# OSP_Carrier_V8_DJB.net
KiCad netlist of a schematic drawn in Altium Designer
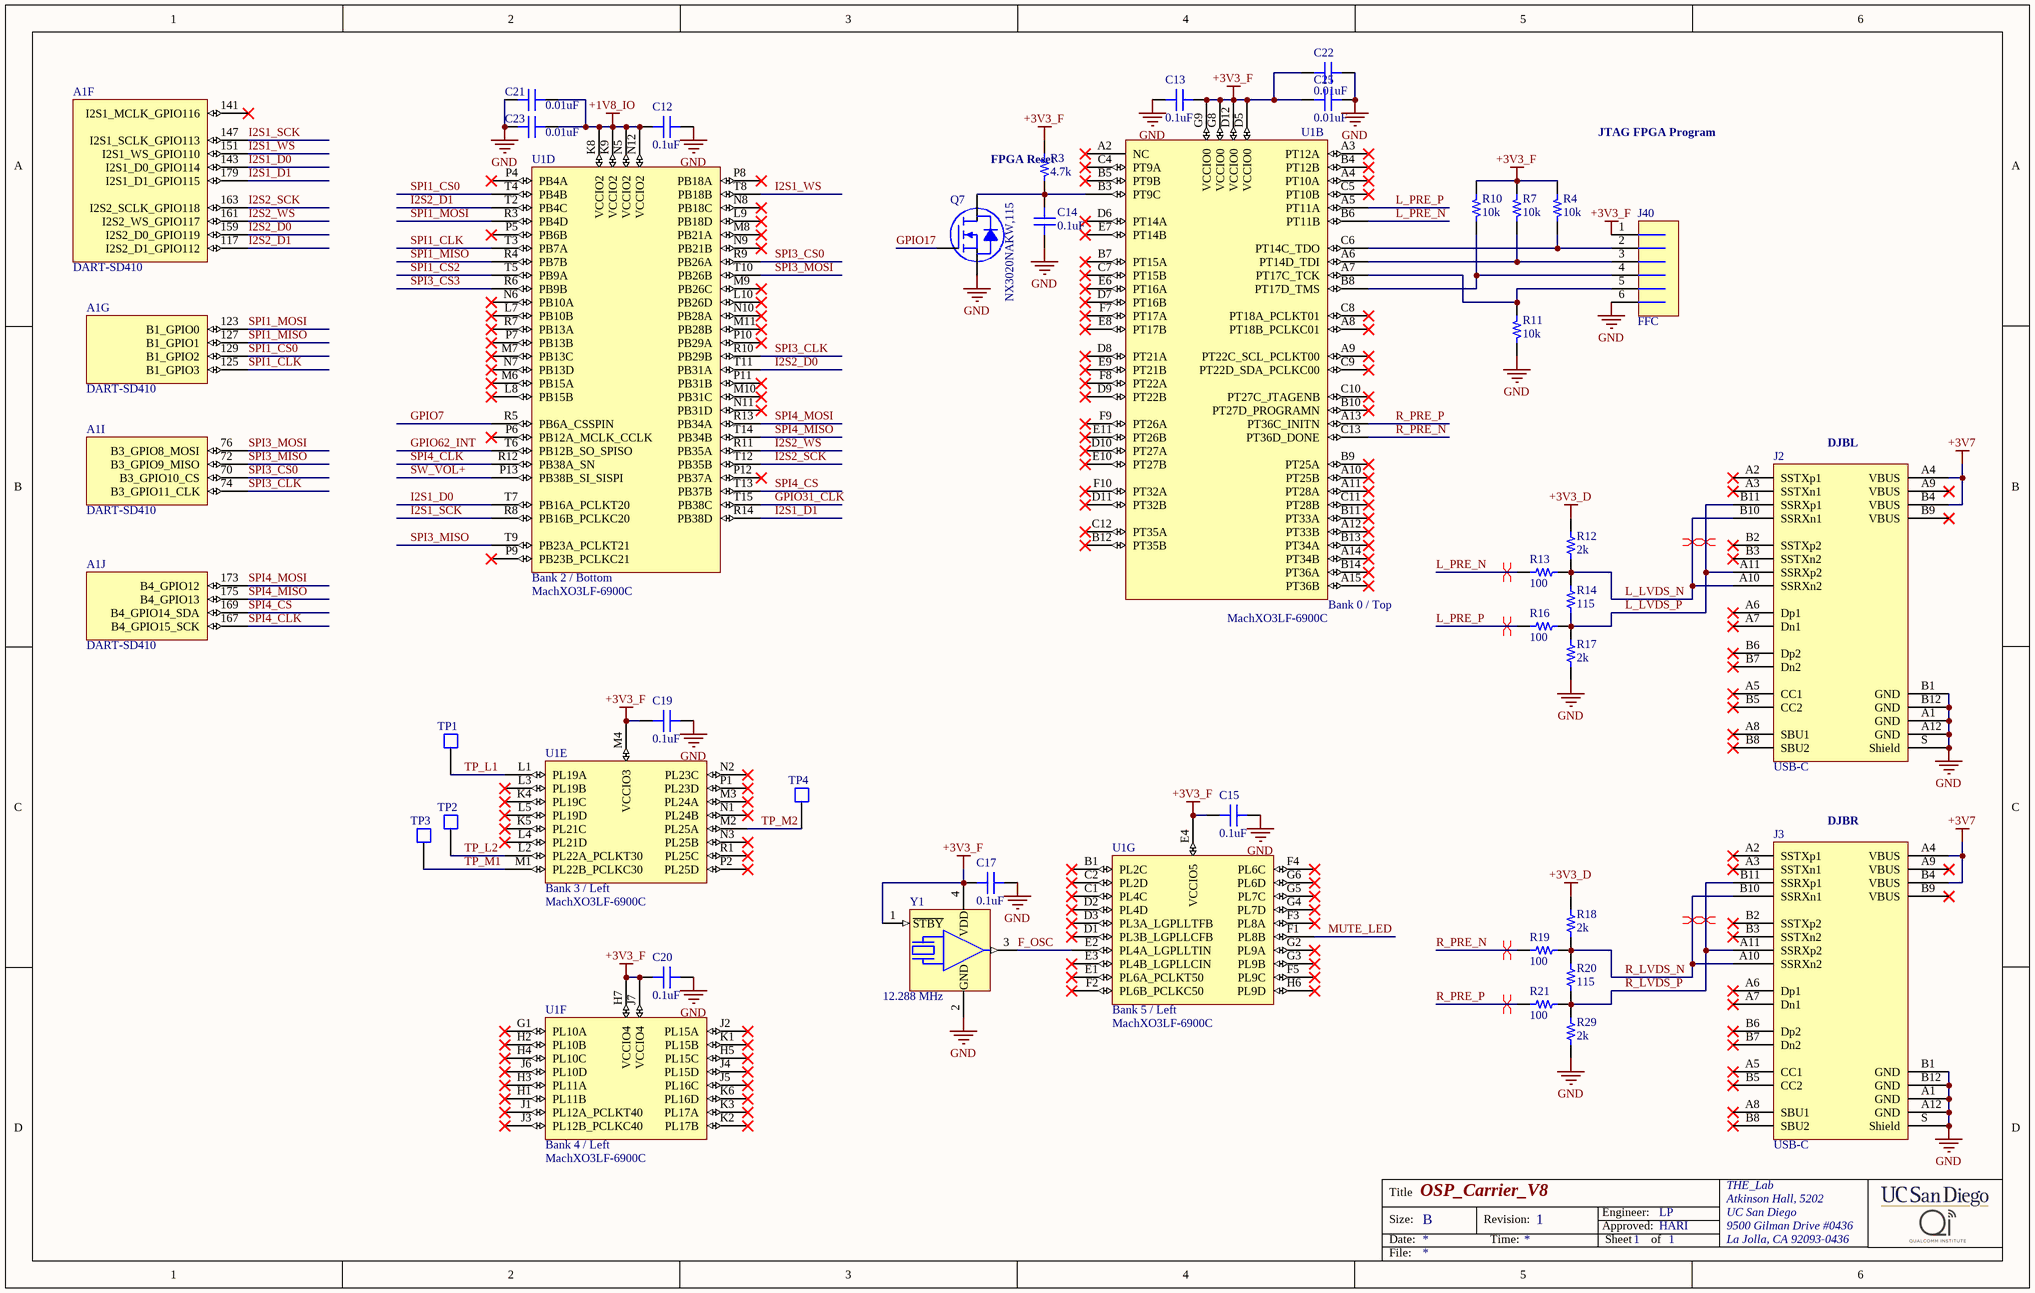
[diagram p0: OSP_Carrier_V8_DJB.SchDoc]

(export (version "E")
  (design (tool "Eeschema 10.0.6"))
  (components
    (comp (ref "A1")
      (value "DART-SD410")
      (footprint "DART-SD410")
      (description "Variscite DART-SD410 System on Module")
      (libsource (lib "DART-SD410") (part "DART-SD410"))
    )
    (comp (ref "C12")
      (value "0.1uF")
      (footprint "CAP 0402/1005")
      (description "CAP CER 0.1UF 50V X7R 0402")
      (fields
        (field (name "PART NUMBER") "C1005X7R1H104K050BB")
        (field (name "MANUFACTURER") "TDK Corporation")
      )
      (libsource (lib "Celestial Library Database") (part "Capacitor"))
    )
    (comp (ref "C13")
      (value "0.1uF")
      (footprint "CAP 0402/1005")
      (description "CAP CER 0.1UF 50V X7R 0402")
      (fields
        (field (name "PART NUMBER") "C1005X7R1H104K050BB")
        (field (name "MANUFACTURER") "TDK Corporation")
      )
      (libsource (lib "Celestial Library Database") (part "Capacitor"))
    )
    (comp (ref "C14")
      (value "0.1uF")
      (footprint "CAP 0402/1005")
      (description "CAP CER 0.1UF 50V X7R 0402")
      (fields
        (field (name "PART NUMBER") "C1005X7R1H104K050BB")
        (field (name "MANUFACTURER") "TDK Corporation")
      )
      (libsource (lib "Celestial Library Database") (part "Capacitor"))
    )
    (comp (ref "C15")
      (value "0.1uF")
      (footprint "CAP 0402/1005")
      (description "CAP CER 0.1UF 50V X7R 0402")
      (fields
        (field (name "PART NUMBER") "C1005X7R1H104K050BB")
        (field (name "MANUFACTURER") "TDK Corporation")
      )
      (libsource (lib "Celestial Library Database") (part "Capacitor"))
    )
    (comp (ref "C17")
      (value "0.1uF")
      (footprint "CAP 0402/1005")
      (description "CAP CER 0.1UF 50V X7R 0402")
      (fields
        (field (name "PART NUMBER") "C1005X7R1H104K050BB")
        (field (name "MANUFACTURER") "TDK Corporation")
      )
      (libsource (lib "Celestial Library Database") (part "Capacitor"))
    )
    (comp (ref "C19")
      (value "0.1uF")
      (footprint "CAP 0402/1005")
      (description "CAP CER 0.1UF 50V X7R 0402")
      (fields
        (field (name "PART NUMBER") "C1005X7R1H104K050BB")
        (field (name "MANUFACTURER") "TDK Corporation")
      )
      (libsource (lib "Celestial Library Database") (part "Capacitor"))
    )
    (comp (ref "C20")
      (value "0.1uF")
      (footprint "CAP 0402/1005")
      (description "CAP CER 0.1UF 50V X7R 0402")
      (fields
        (field (name "PART NUMBER") "C1005X7R1H104K050BB")
        (field (name "MANUFACTURER") "TDK Corporation")
      )
      (libsource (lib "Celestial Library Database") (part "Capacitor"))
    )
    (comp (ref "C21")
      (value "0.01uF")
      (footprint "CAP 0402/1005")
      (description "CAP CER 10000PF 25V X7R 0402")
      (fields (field (name "PART NUMBER") "CC0402KRX7R8BB103") (field (name "MANUFACTURER") "Yageo"))
      (libsource (lib "Celestial Library Database") (part "Capacitor"))
    )
    (comp (ref "C22")
      (value "0.01uF")
      (footprint "CAP 0402/1005")
      (description "CAP CER 10000PF 25V X7R 0402")
      (fields (field (name "PART NUMBER") "CC0402KRX7R8BB103") (field (name "MANUFACTURER") "Yageo"))
      (libsource (lib "Celestial Library Database") (part "Capacitor"))
    )
    (comp (ref "C23")
      (value "0.01uF")
      (footprint "CAP 0402/1005")
      (description "CAP CER 10000PF 25V X7R 0402")
      (fields (field (name "PART NUMBER") "CC0402KRX7R8BB103") (field (name "MANUFACTURER") "Yageo"))
      (libsource (lib "Celestial Library Database") (part "Capacitor"))
    )
    (comp (ref "C25")
      (value "0.01uF")
      (footprint "CAP 0402/1005")
      (description "CAP CER 10000PF 25V X7R 0402")
      (fields (field (name "PART NUMBER") "CC0402KRX7R8BB103") (field (name "MANUFACTURER") "Yageo"))
      (libsource (lib "Celestial Library Database") (part "Capacitor"))
    )
    (comp (ref "J2")
      (value "USB-C")
      (footprint "TE_USB-C_2129691-1")
      (description "TE 2129691-1 USB-C Socket")
      (libsource (lib "OSP_Symbols") (part "TE_USB_C_2129691-1"))
    )
    (comp (ref "J3")
      (value "USB-C")
      (footprint "TE_USB-C_2129691-1")
      (description "TE 2129691-1 USB-C Socket")
      (libsource (lib "OSP_Symbols") (part "TE_USB_C_2129691-1"))
    )
    (comp (ref "J40")
      (value "FFC")
      (footprint "AMPHENOL_HFW6R-1STE1LF")
      (description "Amphenol HFW6R-1STE1LF 6-pin flat flexible cable connector")
      (libsource (lib "OSP_Symbols") (part "AMPHENOL_HFW6R-1STE1LF"))
    )
    (comp (ref "Q7")
      (value "NX3020NAKW,115")
      (footprint "NXP SOT-323-3")
      (description "MOSFET N-CH 30V 180MA SOT323")
      (libsource (lib "Celestial Library Database") (part "NXP MOSFET N-CH SOT-23-3"))
    )
    (comp (ref "R3")
      (value "4.7k")
      (footprint "RES 0402/1005")
      (description "RES SMD 4.7K OHM 1% 1/10W 0402")
      (fields
        (field (name "PART NUMBER") "ERJ-2RKF4701X")
        (field (name "MANUFACTURER") "Panasonic Electronic Components")
      )
      (libsource (lib "Celestial Library Database") (part "Resistor"))
    )
    (comp (ref "R4")
      (value "10k")
      (footprint "RES 0402/1005")
      (description "RES SMD 10K OHM 1% 1/10W 0402")
      (fields
        (field (name "PART NUMBER") "ERJ-2RKF1002X")
        (field (name "MANUFACTURER") "Panasonic Electronic Components")
      )
      (libsource (lib "Celestial Library Database") (part "Resistor"))
    )
    (comp (ref "R7")
      (value "10k")
      (footprint "RES 0402/1005")
      (description "RES SMD 10K OHM 1% 1/10W 0402")
      (fields
        (field (name "PART NUMBER") "ERJ-2RKF1002X")
        (field (name "MANUFACTURER") "Panasonic Electronic Components")
      )
      (libsource (lib "Celestial Library Database") (part "Resistor"))
    )
    (comp (ref "R10")
      (value "10k")
      (footprint "RES 0402/1005")
      (description "RES SMD 10K OHM 1% 1/10W 0402")
      (fields
        (field (name "PART NUMBER") "ERJ-2RKF1002X")
        (field (name "MANUFACTURER") "Panasonic Electronic Components")
      )
      (libsource (lib "Celestial Library Database") (part "Resistor"))
    )
    (comp (ref "R11")
      (value "10k")
      (footprint "RES 0402/1005")
      (description "RES SMD 10K OHM 1% 1/10W 0402")
      (fields
        (field (name "PART NUMBER") "ERJ-2RKF1002X")
        (field (name "MANUFACTURER") "Panasonic Electronic Components")
      )
      (libsource (lib "Celestial Library Database") (part "Resistor"))
    )
    (comp (ref "R12")
      (value "2k")
      (footprint "RES 0402/1005")
      (description "RES SMD 2K OHM 1% 1/10W 0402")
      (fields
        (field (name "PART NUMBER") "ERJ-2RKF2001X")
        (field (name "MANUFACTURER") "Panasonic Electronic Components")
      )
      (libsource (lib "Celestial Library Database") (part "Resistor"))
    )
    (comp (ref "R13")
      (value "100")
      (footprint "RES 0402/1005")
      (description "RES SMD 100 OHM 1% 1/10W 0402")
      (fields
        (field (name "PART NUMBER") "ERJ-2RKF1000X")
        (field (name "MANUFACTURER") "Panasonic Electronic Components")
      )
      (libsource (lib "Celestial Library Database") (part "Resistor"))
    )
    (comp (ref "R14")
      (value "115")
      (footprint "RES 0402/1005")
      (description "RES SMD 115 OHM 1% 1/10W 0402")
      (fields
        (field (name "PART NUMBER") "ERJ-2RKF1150X")
        (field (name "MANUFACTURER") "Panasonic Electronic Components")
      )
      (libsource (lib "Celestial Library Database") (part "Resistor"))
    )
    (comp (ref "R16")
      (value "100")
      (footprint "RES 0402/1005")
      (description "RES SMD 100 OHM 1% 1/10W 0402")
      (fields
        (field (name "PART NUMBER") "ERJ-2RKF1000X")
        (field (name "MANUFACTURER") "Panasonic Electronic Components")
      )
      (libsource (lib "Celestial Library Database") (part "Resistor"))
    )
    (comp (ref "R17")
      (value "2k")
      (footprint "RES 0402/1005")
      (description "RES SMD 2K OHM 1% 1/10W 0402")
      (fields
        (field (name "PART NUMBER") "ERJ-2RKF2001X")
        (field (name "MANUFACTURER") "Panasonic Electronic Components")
      )
      (libsource (lib "Celestial Library Database") (part "Resistor"))
    )
    (comp (ref "R18")
      (value "2k")
      (footprint "RES 0402/1005")
      (description "RES SMD 2K OHM 1% 1/10W 0402")
      (fields
        (field (name "PART NUMBER") "ERJ-2RKF2001X")
        (field (name "MANUFACTURER") "Panasonic Electronic Components")
      )
      (libsource (lib "Celestial Library Database") (part "Resistor"))
    )
    (comp (ref "R19")
      (value "100")
      (footprint "RES 0402/1005")
      (description "RES SMD 100 OHM 1% 1/10W 0402")
      (fields
        (field (name "PART NUMBER") "ERJ-2RKF1000X")
        (field (name "MANUFACTURER") "Panasonic Electronic Components")
      )
      (libsource (lib "Celestial Library Database") (part "Resistor"))
    )
    (comp (ref "R20")
      (value "115")
      (footprint "RES 0402/1005")
      (description "RES SMD 115 OHM 1% 1/10W 0402")
      (fields
        (field (name "PART NUMBER") "ERJ-2RKF1150X")
        (field (name "MANUFACTURER") "Panasonic Electronic Components")
      )
      (libsource (lib "Celestial Library Database") (part "Resistor"))
    )
    (comp (ref "R21")
      (value "100")
      (footprint "RES 0402/1005")
      (description "RES SMD 100 OHM 1% 1/10W 0402")
      (fields
        (field (name "PART NUMBER") "ERJ-2RKF1000X")
        (field (name "MANUFACTURER") "Panasonic Electronic Components")
      )
      (libsource (lib "Celestial Library Database") (part "Resistor"))
    )
    (comp (ref "R29")
      (value "2k")
      (footprint "RES 0402/1005")
      (description "RES SMD 2K OHM 1% 1/10W 0402")
      (fields
        (field (name "PART NUMBER") "ERJ-2RKF2001X")
        (field (name "MANUFACTURER") "Panasonic Electronic Components")
      )
      (libsource (lib "Celestial Library Database") (part "Resistor"))
    )
    (comp (ref "TP1")
      (value "TP_SMD_1MM_SQ")
      (footprint "TP_SMD_1MM_SQ")
      (description "1mm Square SMD Test Point")
      (libsource (lib "OSP_Symbols") (part "TP_SMD_1MM_SQ"))
    )
    (comp (ref "TP2")
      (value "TP_SMD_1MM_SQ")
      (footprint "TP_SMD_1MM_SQ")
      (description "1mm Square SMD Test Point")
      (libsource (lib "OSP_Symbols") (part "TP_SMD_1MM_SQ"))
    )
    (comp (ref "TP3")
      (value "TP_SMD_1MM_SQ")
      (footprint "TP_SMD_1MM_SQ")
      (description "1mm Square SMD Test Point")
      (libsource (lib "OSP_Symbols") (part "TP_SMD_1MM_SQ"))
    )
    (comp (ref "TP4")
      (value "TP_SMD_1MM_SQ")
      (footprint "TP_SMD_1MM_SQ")
      (description "1mm Square SMD Test Point")
      (libsource (lib "OSP_Symbols") (part "TP_SMD_1MM_SQ"))
    )
    (comp (ref "U1")
      (value "MachXO3LF-6900C")
      (footprint "LCMXO3_caBGA_BG256")
      (description "Lattice MachXO3LF-6900C-5BG256C FPGA")
      (libsource (lib "") (part "LCMXO3LF-6900C-XBG256X_1"))
    )
    (comp (ref "Y1")
      (value "12.288 MHz")
      (footprint "OSC_2.5x2.0mm")
      (description "Microchip 12.288 MHz SMD MEMS Oscillator")
      (libsource (lib "OSP_Symbols") (part "MC_DSC1033DI2-012.2880"))
    )
  )
  (nets
    (net (code "1") (name "+1V8_IO") (class "Default")
      (node (ref "C12") (pin "2") (pinfunction "2_2") (pintype "passive"))
      (node (ref "C21") (pin "1") (pinfunction "1_1") (pintype "passive"))
      (node (ref "C23") (pin "1") (pinfunction "1_1") (pintype "passive"))
      (node (ref "U1") (pin "K8") (pinfunction "VCCIO2_K8") (pintype "bidirectional"))
      (node (ref "U1") (pin "K9") (pinfunction "VCCIO2_K9") (pintype "bidirectional"))
      (node (ref "U1") (pin "N12") (pinfunction "VCCIO2_N12") (pintype "bidirectional"))
      (node (ref "U1") (pin "N5") (pinfunction "VCCIO2_N5") (pintype "bidirectional"))
    )
    (net (code "2") (name "+3V3_D") (class "Default")
      (node (ref "R12") (pin "2") (pinfunction "2_2") (pintype "passive"))
      (node (ref "R18") (pin "2") (pinfunction "2_2") (pintype "passive"))
    )
    (net (code "3") (name "+3V3_F") (class "Default")
      (node (ref "C13") (pin "2") (pinfunction "2_2") (pintype "passive"))
      (node (ref "C15") (pin "2") (pinfunction "2_2") (pintype "passive"))
      (node (ref "C17") (pin "2") (pinfunction "2_2") (pintype "passive"))
      (node (ref "C19") (pin "2") (pinfunction "2_2") (pintype "passive"))
      (node (ref "C20") (pin "2") (pinfunction "2_2") (pintype "passive"))
      (node (ref "C22") (pin "1") (pinfunction "1_1") (pintype "passive"))
      (node (ref "C25") (pin "1") (pinfunction "1_1") (pintype "passive"))
      (node (ref "J40") (pin "1") (pintype "passive"))
      (node (ref "R10") (pin "2") (pinfunction "2_2") (pintype "passive"))
      (node (ref "R3") (pin "2") (pinfunction "2_2") (pintype "passive"))
      (node (ref "R4") (pin "2") (pinfunction "2_2") (pintype "passive"))
      (node (ref "R7") (pin "2") (pinfunction "2_2") (pintype "passive"))
      (node (ref "U1") (pin "D12") (pinfunction "VCCIO0_D12") (pintype "bidirectional"))
      (node (ref "U1") (pin "D5") (pinfunction "VCCIO0_D5") (pintype "bidirectional"))
      (node (ref "U1") (pin "E4") (pinfunction "VCCIO5_E4") (pintype "bidirectional"))
      (node (ref "U1") (pin "G8") (pinfunction "VCCIO0_G8") (pintype "bidirectional"))
      (node (ref "U1") (pin "G9") (pinfunction "VCCIO0_G9") (pintype "bidirectional"))
      (node (ref "U1") (pin "H7") (pinfunction "VCCIO4_H7") (pintype "bidirectional"))
      (node (ref "U1") (pin "J7") (pinfunction "VCCIO4_J7") (pintype "bidirectional"))
      (node (ref "U1") (pin "M4") (pinfunction "VCCIO3_M4") (pintype "bidirectional"))
      (node (ref "Y1") (pin "1") (pinfunction "~{STBY}_1") (pintype "input"))
      (node (ref "Y1") (pin "4") (pinfunction "VDD_4") (pintype "power_in"))
    )
    (net (code "4") (name "+3V7") (class "Default")
      (node (ref "J2") (pin "A4") (pinfunction "VBUS_A4") (pintype "passive"))
      (node (ref "J2") (pin "B4") (pinfunction "VBUS_B4") (pintype "passive"))
      (node (ref "J3") (pin "A4") (pinfunction "VBUS_A4") (pintype "passive"))
      (node (ref "J3") (pin "B4") (pinfunction "VBUS_B4") (pintype "passive"))
    )
    (net (code "5") (name "/F_OSC") (class "Default")
      (node (ref "U1") (pin "E2") (pinfunction "PL4A_LGPLLTIN_E2") (pintype "bidirectional"))
      (node (ref "Y1") (pin "3") (pinfunction "OUT_3") (pintype "output"))
    )
    (net (code "6") (name "/GPIO7") (class "Default")
      (node (ref "U1") (pin "R5") (pinfunction "PB6A_CSSPIN_R5") (pintype "bidirectional"))
    )
    (net (code "7") (name "/GPIO17") (class "Default")
      (node (ref "Q7") (pin "1") (pinfunction "G_1") (pintype "passive"))
    )
    (net (code "8") (name "/GPIO31_CLK") (class "Default")
      (node (ref "U1") (pin "T15") (pinfunction "PB38C_T15") (pintype "bidirectional"))
    )
    (net (code "9") (name "/GPIO62_INT") (class "Default")
      (node (ref "U1") (pin "T6") (pinfunction "PB12B_SO_SPISO_T6") (pintype "bidirectional"))
    )
    (net (code "10") (name "/I2S1_D0") (class "Default")
      (node (ref "A1") (pin "143") (pinfunction "I2S1_D0_GPIO114_143") (pintype "bidirectional"))
      (node (ref "U1") (pin "T7") (pinfunction "PB16A_PCLKT20_T7") (pintype "bidirectional"))
    )
    (net (code "11") (name "/I2S1_D1") (class "Default")
      (node (ref "A1") (pin "179") (pinfunction "I2S1_D1_GPIO115_179") (pintype "bidirectional"))
      (node (ref "U1") (pin "R14") (pinfunction "PB38D_R14") (pintype "bidirectional"))
    )
    (net (code "12") (name "/I2S1_SCK") (class "Default")
      (node (ref "A1") (pin "147") (pinfunction "I2S1_SCLK_GPIO113_147") (pintype "bidirectional"))
      (node (ref "U1") (pin "R8") (pinfunction "PB16B_PCLKC20_R8") (pintype "bidirectional"))
    )
    (net (code "13") (name "/I2S1_WS") (class "Default")
      (node (ref "A1") (pin "151") (pinfunction "I2S1_WS_GPIO110_151") (pintype "bidirectional"))
      (node (ref "U1") (pin "T8") (pinfunction "PB18B_T8") (pintype "bidirectional"))
    )
    (net (code "14") (name "/I2S2_D0") (class "Default")
      (node (ref "A1") (pin "159") (pinfunction "I2S2_D0_GPIO119_159") (pintype "bidirectional"))
      (node (ref "U1") (pin "T11") (pinfunction "PB31A_T11") (pintype "bidirectional"))
    )
    (net (code "15") (name "/I2S2_D1") (class "Default")
      (node (ref "A1") (pin "117") (pinfunction "I2S2_D1_GPIO112_117") (pintype "bidirectional"))
      (node (ref "U1") (pin "T2") (pinfunction "PB4C_T2") (pintype "bidirectional"))
    )
    (net (code "16") (name "/I2S2_SCK") (class "Default")
      (node (ref "A1") (pin "163") (pinfunction "I2S2_SCLK_GPIO118_163") (pintype "bidirectional"))
      (node (ref "U1") (pin "T12") (pinfunction "PB35B_T12") (pintype "bidirectional"))
    )
    (net (code "17") (name "/I2S2_WS") (class "Default")
      (node (ref "A1") (pin "161") (pinfunction "I2S2_WS_GPIO117_161") (pintype "bidirectional"))
      (node (ref "U1") (pin "R11") (pinfunction "PB35A_R11") (pintype "bidirectional"))
    )
    (net (code "18") (name "/L_LVDS_N") (class "Default")
      (node (ref "J2") (pin "A10") (pinfunction "SSRXn2_A10") (pintype "passive"))
      (node (ref "J2") (pin "B10") (pinfunction "SSRXn1_B10") (pintype "passive"))
      (node (ref "R12") (pin "1") (pinfunction "1_1") (pintype "passive"))
      (node (ref "R13") (pin "2") (pinfunction "2_2") (pintype "passive"))
      (node (ref "R14") (pin "2") (pinfunction "2_2") (pintype "passive"))
    )
    (net (code "19") (name "/L_LVDS_P") (class "Default")
      (node (ref "J2") (pin "A11") (pinfunction "SSRXp2_A11") (pintype "passive"))
      (node (ref "J2") (pin "B11") (pinfunction "SSRXp1_B11") (pintype "passive"))
      (node (ref "R14") (pin "1") (pinfunction "1_1") (pintype "passive"))
      (node (ref "R16") (pin "2") (pinfunction "2_2") (pintype "passive"))
      (node (ref "R17") (pin "2") (pinfunction "2_2") (pintype "passive"))
    )
    (net (code "20") (name "/L_PRE_N") (class "Default")
      (node (ref "R13") (pin "1") (pinfunction "1_1") (pintype "passive"))
      (node (ref "U1") (pin "B6") (pinfunction "PT11B_B6") (pintype "bidirectional"))
    )
    (net (code "21") (name "/L_PRE_P") (class "Default")
      (node (ref "R16") (pin "1") (pinfunction "1_1") (pintype "passive"))
      (node (ref "U1") (pin "A5") (pinfunction "PT11A_A5") (pintype "bidirectional"))
    )
    (net (code "22") (name "/MUTE_LED") (class "Default")
      (node (ref "U1") (pin "F1") (pinfunction "PL8B_F1") (pintype "bidirectional"))
    )
    (net (code "23") (name "/R_LVDS_N") (class "Default")
      (node (ref "J3") (pin "A10") (pinfunction "SSRXn2_A10") (pintype "passive"))
      (node (ref "J3") (pin "B10") (pinfunction "SSRXn1_B10") (pintype "passive"))
      (node (ref "R18") (pin "1") (pinfunction "1_1") (pintype "passive"))
      (node (ref "R19") (pin "2") (pinfunction "2_2") (pintype "passive"))
      (node (ref "R20") (pin "2") (pinfunction "2_2") (pintype "passive"))
    )
    (net (code "24") (name "/R_LVDS_P") (class "Default")
      (node (ref "J3") (pin "A11") (pinfunction "SSRXp2_A11") (pintype "passive"))
      (node (ref "J3") (pin "B11") (pinfunction "SSRXp1_B11") (pintype "passive"))
      (node (ref "R20") (pin "1") (pinfunction "1_1") (pintype "passive"))
      (node (ref "R21") (pin "2") (pinfunction "2_2") (pintype "passive"))
      (node (ref "R29") (pin "2") (pinfunction "2_2") (pintype "passive"))
    )
    (net (code "25") (name "/R_PRE_N") (class "Default")
      (node (ref "R19") (pin "1") (pinfunction "1_1") (pintype "passive"))
      (node (ref "U1") (pin "C13") (pinfunction "PT36D_DONE_C13") (pintype "bidirectional"))
    )
    (net (code "26") (name "/R_PRE_P") (class "Default")
      (node (ref "R21") (pin "1") (pinfunction "1_1") (pintype "passive"))
      (node (ref "U1") (pin "A13") (pinfunction "PT36C_INITN_A13") (pintype "bidirectional"))
    )
    (net (code "27") (name "/SPI1_CLK") (class "Default")
      (node (ref "A1") (pin "125") (pinfunction "B1_GPIO3_125") (pintype "bidirectional"))
      (node (ref "U1") (pin "T3") (pinfunction "PB7A_T3") (pintype "bidirectional"))
    )
    (net (code "28") (name "/SPI1_CS0") (class "Default")
      (node (ref "A1") (pin "129") (pinfunction "B1_GPIO2_129") (pintype "bidirectional"))
      (node (ref "U1") (pin "T4") (pinfunction "PB4B_T4") (pintype "bidirectional"))
    )
    (net (code "29") (name "/SPI1_CS2") (class "Default")
      (node (ref "U1") (pin "T5") (pinfunction "PB9A_T5") (pintype "bidirectional"))
    )
    (net (code "30") (name "/SPI1_MISO") (class "Default")
      (node (ref "A1") (pin "127") (pinfunction "B1_GPIO1_127") (pintype "bidirectional"))
      (node (ref "U1") (pin "R4") (pinfunction "PB7B_R4") (pintype "bidirectional"))
    )
    (net (code "31") (name "/SPI1_MOSI") (class "Default")
      (node (ref "A1") (pin "123") (pinfunction "B1_GPIO0_123") (pintype "bidirectional"))
      (node (ref "U1") (pin "R3") (pinfunction "PB4D_R3") (pintype "bidirectional"))
    )
    (net (code "32") (name "/SPI3_CLK") (class "Default")
      (node (ref "A1") (pin "74") (pinfunction "B3_GPIO11_CLK_74") (pintype "bidirectional"))
      (node (ref "U1") (pin "R10") (pinfunction "PB29B_R10") (pintype "bidirectional"))
    )
    (net (code "33") (name "/SPI3_CS0") (class "Default")
      (node (ref "A1") (pin "70") (pinfunction "B3_GPIO10_CS_70") (pintype "bidirectional"))
      (node (ref "U1") (pin "R9") (pinfunction "PB26A_R9") (pintype "bidirectional"))
    )
    (net (code "34") (name "/SPI3_CS3") (class "Default")
      (node (ref "U1") (pin "R6") (pinfunction "PB9B_R6") (pintype "bidirectional"))
    )
    (net (code "35") (name "/SPI3_MISO") (class "Default")
      (node (ref "A1") (pin "72") (pinfunction "B3_GPIO9_MISO_72") (pintype "bidirectional"))
      (node (ref "U1") (pin "T9") (pinfunction "PB23A_PCLKT21_T9") (pintype "bidirectional"))
    )
    (net (code "36") (name "/SPI3_MOSI") (class "Default")
      (node (ref "A1") (pin "76") (pinfunction "B3_GPIO8_MOSI_76") (pintype "bidirectional"))
      (node (ref "U1") (pin "T10") (pinfunction "PB26B_T10") (pintype "bidirectional"))
    )
    (net (code "37") (name "/SPI4_CLK") (class "Default")
      (node (ref "A1") (pin "167") (pinfunction "B4_GPIO15_SCK_167") (pintype "bidirectional"))
      (node (ref "U1") (pin "R12") (pinfunction "PB38A_SN_R12") (pintype "bidirectional"))
    )
    (net (code "38") (name "/SPI4_CS") (class "Default")
      (node (ref "A1") (pin "169") (pinfunction "B4_GPIO14_SDA_169") (pintype "bidirectional"))
      (node (ref "U1") (pin "T13") (pinfunction "PB37B_T13") (pintype "bidirectional"))
    )
    (net (code "39") (name "/SPI4_MISO") (class "Default")
      (node (ref "A1") (pin "175") (pinfunction "B4_GPIO13_175") (pintype "bidirectional"))
      (node (ref "U1") (pin "T14") (pinfunction "PB34B_T14") (pintype "bidirectional"))
    )
    (net (code "40") (name "/SPI4_MOSI") (class "Default")
      (node (ref "A1") (pin "173") (pinfunction "B4_GPIO12_173") (pintype "bidirectional"))
      (node (ref "U1") (pin "R13") (pinfunction "PB34A_R13") (pintype "bidirectional"))
    )
    (net (code "41") (name "/SW_VOL+") (class "Default")
      (node (ref "U1") (pin "P13") (pinfunction "PB38B_SI_SISPI_P13") (pintype "bidirectional"))
    )
    (net (code "42") (name "/TP_L1") (class "Default")
      (node (ref "TP1") (pin "1") (pintype "passive"))
      (node (ref "U1") (pin "L1") (pinfunction "PL19A_L1") (pintype "bidirectional"))
    )
    (net (code "43") (name "/TP_L2") (class "Default")
      (node (ref "TP2") (pin "1") (pintype "passive"))
      (node (ref "U1") (pin "L2") (pinfunction "PL22A_PCLKT30_L2") (pintype "bidirectional"))
    )
    (net (code "44") (name "/TP_M1") (class "Default")
      (node (ref "TP3") (pin "1") (pintype "passive"))
      (node (ref "U1") (pin "M1") (pinfunction "PL22B_PCLKC30_M1") (pintype "bidirectional"))
    )
    (net (code "45") (name "/TP_M2") (class "Default")
      (node (ref "TP4") (pin "1") (pintype "passive"))
      (node (ref "U1") (pin "M2") (pinfunction "PL25A_M2") (pintype "bidirectional"))
    )
    (net (code "46") (name "GND") (class "Default")
      (node (ref "C12") (pin "1") (pinfunction "1_1") (pintype "passive"))
      (node (ref "C13") (pin "1") (pinfunction "1_1") (pintype "passive"))
      (node (ref "C14") (pin "2") (pinfunction "2_2") (pintype "passive"))
      (node (ref "C15") (pin "1") (pinfunction "1_1") (pintype "passive"))
      (node (ref "C17") (pin "1") (pinfunction "1_1") (pintype "passive"))
      (node (ref "C19") (pin "1") (pinfunction "1_1") (pintype "passive"))
      (node (ref "C20") (pin "1") (pinfunction "1_1") (pintype "passive"))
      (node (ref "C21") (pin "2") (pinfunction "2_2") (pintype "passive"))
      (node (ref "C22") (pin "2") (pinfunction "2_2") (pintype "passive"))
      (node (ref "C23") (pin "2") (pinfunction "2_2") (pintype "passive"))
      (node (ref "C25") (pin "2") (pinfunction "2_2") (pintype "passive"))
      (node (ref "J2") (pin "A1") (pinfunction "GND_A1") (pintype "passive"))
      (node (ref "J2") (pin "A12") (pinfunction "GND_A12") (pintype "passive"))
      (node (ref "J2") (pin "B1") (pinfunction "GND_B1") (pintype "passive"))
      (node (ref "J2") (pin "B12") (pinfunction "GND_B12") (pintype "passive"))
      (node (ref "J2") (pin "S") (pinfunction "Shield_S") (pintype "passive"))
      (node (ref "J3") (pin "A1") (pinfunction "GND_A1") (pintype "passive"))
      (node (ref "J3") (pin "A12") (pinfunction "GND_A12") (pintype "passive"))
      (node (ref "J3") (pin "B1") (pinfunction "GND_B1") (pintype "passive"))
      (node (ref "J3") (pin "B12") (pinfunction "GND_B12") (pintype "passive"))
      (node (ref "J3") (pin "S") (pinfunction "Shield_S") (pintype "passive"))
      (node (ref "J40") (pin "6") (pintype "passive"))
      (node (ref "Q7") (pin "3") (pinfunction "S_3") (pintype "passive"))
      (node (ref "R11") (pin "1") (pinfunction "1_1") (pintype "passive"))
      (node (ref "R17") (pin "1") (pinfunction "1_1") (pintype "passive"))
      (node (ref "R29") (pin "1") (pinfunction "1_1") (pintype "passive"))
      (node (ref "Y1") (pin "2") (pinfunction "GND_2") (pintype "power_in"))
    )
    (net (code "47") (name "Net-(Q7-D)") (class "Default")
      (node (ref "C14") (pin "1") (pinfunction "1_1") (pintype "passive"))
      (node (ref "Q7") (pin "2") (pinfunction "D_2") (pintype "passive"))
      (node (ref "R3") (pin "1") (pinfunction "1_1") (pintype "passive"))
      (node (ref "U1") (pin "B3") (pinfunction "PT9C_B3") (pintype "bidirectional"))
    )
    (net (code "48") (name "Net-(U1B-PT14C_TDO)") (class "Default")
      (node (ref "J40") (pin "2") (pintype "passive"))
      (node (ref "R4") (pin "1") (pinfunction "1_1") (pintype "passive"))
      (node (ref "U1") (pin "C6") (pinfunction "PT14C_TDO_C6") (pintype "bidirectional"))
    )
    (net (code "49") (name "Net-(U1B-PT14D_TDI)") (class "Default")
      (node (ref "J40") (pin "3") (pintype "passive"))
      (node (ref "R7") (pin "1") (pinfunction "1_1") (pintype "passive"))
      (node (ref "U1") (pin "A6") (pinfunction "PT14D_TDI_A6") (pintype "bidirectional"))
    )
    (net (code "50") (name "Net-(U1B-PT17C_TCK)") (class "Default")
      (node (ref "J40") (pin "5") (pintype "passive"))
      (node (ref "R11") (pin "2") (pinfunction "2_2") (pintype "passive"))
      (node (ref "U1") (pin "A7") (pinfunction "PT17C_TCK_A7") (pintype "bidirectional"))
    )
    (net (code "51") (name "Net-(U1B-PT17D_TMS)") (class "Default")
      (node (ref "J40") (pin "4") (pintype "passive"))
      (node (ref "R10") (pin "1") (pinfunction "1_1") (pintype "passive"))
      (node (ref "U1") (pin "B8") (pinfunction "PT17D_TMS_B8") (pintype "bidirectional"))
    )
    (net (code "52") (name "unconnected-(A1F-I2S1_MCLK_GPIO116-Pad141)") (class "Default")
      (node (ref "A1") (pin "141") (pinfunction "I2S1_MCLK_GPIO116_141") (pintype "bidirectional+no_connect"))
    )
    (net (code "53") (name "unconnected-(J2-CC1-PadA5)") (class "Default")
      (node (ref "J2") (pin "A5") (pinfunction "CC1_A5") (pintype "passive+no_connect"))
    )
    (net (code "54") (name "unconnected-(J2-CC2-PadB5)") (class "Default")
      (node (ref "J2") (pin "B5") (pinfunction "CC2_B5") (pintype "passive+no_connect"))
    )
    (net (code "55") (name "unconnected-(J2-Dn1-PadA7)") (class "Default")
      (node (ref "J2") (pin "A7") (pinfunction "Dn1_A7") (pintype "passive+no_connect"))
    )
    (net (code "56") (name "unconnected-(J2-Dn2-PadB7)") (class "Default")
      (node (ref "J2") (pin "B7") (pinfunction "Dn2_B7") (pintype "passive+no_connect"))
    )
    (net (code "57") (name "unconnected-(J2-Dp1-PadA6)") (class "Default")
      (node (ref "J2") (pin "A6") (pinfunction "Dp1_A6") (pintype "passive+no_connect"))
    )
    (net (code "58") (name "unconnected-(J2-Dp2-PadB6)") (class "Default")
      (node (ref "J2") (pin "B6") (pinfunction "Dp2_B6") (pintype "passive+no_connect"))
    )
    (net (code "59") (name "unconnected-(J2-SBU1-PadA8)") (class "Default")
      (node (ref "J2") (pin "A8") (pinfunction "SBU1_A8") (pintype "passive+no_connect"))
    )
    (net (code "60") (name "unconnected-(J2-SBU2-PadB8)") (class "Default")
      (node (ref "J2") (pin "B8") (pinfunction "SBU2_B8") (pintype "passive+no_connect"))
    )
    (net (code "61") (name "unconnected-(J2-SSTXn1-PadA3)") (class "Default")
      (node (ref "J2") (pin "A3") (pinfunction "SSTXn1_A3") (pintype "passive+no_connect"))
    )
    (net (code "62") (name "unconnected-(J2-SSTXn2-PadB3)") (class "Default")
      (node (ref "J2") (pin "B3") (pinfunction "SSTXn2_B3") (pintype "passive+no_connect"))
    )
    (net (code "63") (name "unconnected-(J2-SSTXp1-PadA2)") (class "Default")
      (node (ref "J2") (pin "A2") (pinfunction "SSTXp1_A2") (pintype "passive+no_connect"))
    )
    (net (code "64") (name "unconnected-(J2-SSTXp2-PadB2)") (class "Default")
      (node (ref "J2") (pin "B2") (pinfunction "SSTXp2_B2") (pintype "passive+no_connect"))
    )
    (net (code "65") (name "unconnected-(J2-VBUS-PadA9)") (class "Default")
      (node (ref "J2") (pin "A9") (pinfunction "VBUS_A9") (pintype "passive+no_connect"))
    )
    (net (code "66") (name "unconnected-(J2-VBUS-PadB9)") (class "Default")
      (node (ref "J2") (pin "B9") (pinfunction "VBUS_B9") (pintype "passive+no_connect"))
    )
    (net (code "67") (name "unconnected-(J3-CC1-PadA5)") (class "Default")
      (node (ref "J3") (pin "A5") (pinfunction "CC1_A5") (pintype "passive+no_connect"))
    )
    (net (code "68") (name "unconnected-(J3-CC2-PadB5)") (class "Default")
      (node (ref "J3") (pin "B5") (pinfunction "CC2_B5") (pintype "passive+no_connect"))
    )
    (net (code "69") (name "unconnected-(J3-Dn1-PadA7)") (class "Default")
      (node (ref "J3") (pin "A7") (pinfunction "Dn1_A7") (pintype "passive+no_connect"))
    )
    (net (code "70") (name "unconnected-(J3-Dn2-PadB7)") (class "Default")
      (node (ref "J3") (pin "B7") (pinfunction "Dn2_B7") (pintype "passive+no_connect"))
    )
    (net (code "71") (name "unconnected-(J3-Dp1-PadA6)") (class "Default")
      (node (ref "J3") (pin "A6") (pinfunction "Dp1_A6") (pintype "passive+no_connect"))
    )
    (net (code "72") (name "unconnected-(J3-Dp2-PadB6)") (class "Default")
      (node (ref "J3") (pin "B6") (pinfunction "Dp2_B6") (pintype "passive+no_connect"))
    )
    (net (code "73") (name "unconnected-(J3-SBU1-PadA8)") (class "Default")
      (node (ref "J3") (pin "A8") (pinfunction "SBU1_A8") (pintype "passive+no_connect"))
    )
    (net (code "74") (name "unconnected-(J3-SBU2-PadB8)") (class "Default")
      (node (ref "J3") (pin "B8") (pinfunction "SBU2_B8") (pintype "passive+no_connect"))
    )
    (net (code "75") (name "unconnected-(J3-SSTXn1-PadA3)") (class "Default")
      (node (ref "J3") (pin "A3") (pinfunction "SSTXn1_A3") (pintype "passive+no_connect"))
    )
    (net (code "76") (name "unconnected-(J3-SSTXn2-PadB3)") (class "Default")
      (node (ref "J3") (pin "B3") (pinfunction "SSTXn2_B3") (pintype "passive+no_connect"))
    )
    (net (code "77") (name "unconnected-(J3-SSTXp1-PadA2)") (class "Default")
      (node (ref "J3") (pin "A2") (pinfunction "SSTXp1_A2") (pintype "passive+no_connect"))
    )
    (net (code "78") (name "unconnected-(J3-SSTXp2-PadB2)") (class "Default")
      (node (ref "J3") (pin "B2") (pinfunction "SSTXp2_B2") (pintype "passive+no_connect"))
    )
    (net (code "79") (name "unconnected-(J3-VBUS-PadA9)") (class "Default")
      (node (ref "J3") (pin "A9") (pinfunction "VBUS_A9") (pintype "passive+no_connect"))
    )
    (net (code "80") (name "unconnected-(J3-VBUS-PadB9)") (class "Default")
      (node (ref "J3") (pin "B9") (pinfunction "VBUS_B9") (pintype "passive+no_connect"))
    )
    (net (code "81") (name "unconnected-(U1B-NC-PadA2)") (class "Default")
      (node (ref "U1") (pin "A2") (pinfunction "NC_A2") (pintype "passive+no_connect"))
    )
    (net (code "82") (name "unconnected-(U1B-PT9A-PadC4)") (class "Default")
      (node (ref "U1") (pin "C4") (pinfunction "PT9A_C4") (pintype "bidirectional+no_connect"))
    )
    (net (code "83") (name "unconnected-(U1B-PT9B-PadB5)") (class "Default")
      (node (ref "U1") (pin "B5") (pinfunction "PT9B_B5") (pintype "bidirectional+no_connect"))
    )
    (net (code "84") (name "unconnected-(U1B-PT10A-PadA4)") (class "Default")
      (node (ref "U1") (pin "A4") (pinfunction "PT10A_A4") (pintype "bidirectional+no_connect"))
    )
    (net (code "85") (name "unconnected-(U1B-PT10B-PadC5)") (class "Default")
      (node (ref "U1") (pin "C5") (pinfunction "PT10B_C5") (pintype "bidirectional+no_connect"))
    )
    (net (code "86") (name "unconnected-(U1B-PT12A-PadA3)") (class "Default")
      (node (ref "U1") (pin "A3") (pinfunction "PT12A_A3") (pintype "bidirectional+no_connect"))
    )
    (net (code "87") (name "unconnected-(U1B-PT12B-PadB4)") (class "Default")
      (node (ref "U1") (pin "B4") (pinfunction "PT12B_B4") (pintype "bidirectional+no_connect"))
    )
    (net (code "88") (name "unconnected-(U1B-PT14A-PadD6)") (class "Default")
      (node (ref "U1") (pin "D6") (pinfunction "PT14A_D6") (pintype "bidirectional+no_connect"))
    )
    (net (code "89") (name "unconnected-(U1B-PT14B-PadE7)") (class "Default")
      (node (ref "U1") (pin "E7") (pinfunction "PT14B_E7") (pintype "bidirectional+no_connect"))
    )
    (net (code "90") (name "unconnected-(U1B-PT15A-PadB7)") (class "Default")
      (node (ref "U1") (pin "B7") (pinfunction "PT15A_B7") (pintype "bidirectional+no_connect"))
    )
    (net (code "91") (name "unconnected-(U1B-PT15B-PadC7)") (class "Default")
      (node (ref "U1") (pin "C7") (pinfunction "PT15B_C7") (pintype "bidirectional+no_connect"))
    )
    (net (code "92") (name "unconnected-(U1B-PT16A-PadE6)") (class "Default")
      (node (ref "U1") (pin "E6") (pinfunction "PT16A_E6") (pintype "bidirectional+no_connect"))
    )
    (net (code "93") (name "unconnected-(U1B-PT16B-PadD7)") (class "Default")
      (node (ref "U1") (pin "D7") (pinfunction "PT16B_D7") (pintype "bidirectional+no_connect"))
    )
    (net (code "94") (name "unconnected-(U1B-PT17A-PadF7)") (class "Default")
      (node (ref "U1") (pin "F7") (pinfunction "PT17A_F7") (pintype "bidirectional+no_connect"))
    )
    (net (code "95") (name "unconnected-(U1B-PT17B-PadE8)") (class "Default")
      (node (ref "U1") (pin "E8") (pinfunction "PT17B_E8") (pintype "bidirectional+no_connect"))
    )
    (net (code "96") (name "unconnected-(U1B-PT18A_PCLKT01-PadC8)") (class "Default")
      (node (ref "U1") (pin "C8") (pinfunction "PT18A_PCLKT01_C8") (pintype "bidirectional+no_connect"))
    )
    (net (code "97") (name "unconnected-(U1B-PT18B_PCLKC01-PadA8)") (class "Default")
      (node (ref "U1") (pin "A8") (pinfunction "PT18B_PCLKC01_A8") (pintype "bidirectional+no_connect"))
    )
    (net (code "98") (name "unconnected-(U1B-PT21A-PadD8)") (class "Default")
      (node (ref "U1") (pin "D8") (pinfunction "PT21A_D8") (pintype "bidirectional+no_connect"))
    )
    (net (code "99") (name "unconnected-(U1B-PT21B-PadE9)") (class "Default")
      (node (ref "U1") (pin "E9") (pinfunction "PT21B_E9") (pintype "bidirectional+no_connect"))
    )
    (net (code "100") (name "unconnected-(U1B-PT22A-PadF8)") (class "Default")
      (node (ref "U1") (pin "F8") (pinfunction "PT22A_F8") (pintype "bidirectional+no_connect"))
    )
    (net (code "101") (name "unconnected-(U1B-PT22B-PadD9)") (class "Default")
      (node (ref "U1") (pin "D9") (pinfunction "PT22B_D9") (pintype "bidirectional+no_connect"))
    )
    (net (code "102") (name "unconnected-(U1B-PT22C_SCL_PCLKT00-PadA9)") (class "Default")
      (node (ref "U1") (pin "A9") (pinfunction "PT22C_SCL_PCLKT00_A9") (pintype "bidirectional+no_connect"))
    )
    (net (code "103") (name "unconnected-(U1B-PT22D_SDA_PCLKC00-PadC9)") (class "Default")
      (node (ref "U1") (pin "C9") (pinfunction "PT22D_SDA_PCLKC00_C9") (pintype "bidirectional+no_connect"))
    )
    (net (code "104") (name "unconnected-(U1B-PT25A-PadB9)") (class "Default")
      (node (ref "U1") (pin "B9") (pinfunction "PT25A_B9") (pintype "bidirectional+no_connect"))
    )
    (net (code "105") (name "unconnected-(U1B-PT25B-PadA10)") (class "Default")
      (node (ref "U1") (pin "A10") (pinfunction "PT25B_A10") (pintype "bidirectional+no_connect"))
    )
    (net (code "106") (name "unconnected-(U1B-PT26A-PadF9)") (class "Default")
      (node (ref "U1") (pin "F9") (pinfunction "PT26A_F9") (pintype "bidirectional+no_connect"))
    )
    (net (code "107") (name "unconnected-(U1B-PT26B-PadE11)") (class "Default")
      (node (ref "U1") (pin "E11") (pinfunction "PT26B_E11") (pintype "bidirectional+no_connect"))
    )
    (net (code "108") (name "unconnected-(U1B-PT27A-PadD10)") (class "Default")
      (node (ref "U1") (pin "D10") (pinfunction "PT27A_D10") (pintype "bidirectional+no_connect"))
    )
    (net (code "109") (name "unconnected-(U1B-PT27B-PadE10)") (class "Default")
      (node (ref "U1") (pin "E10") (pinfunction "PT27B_E10") (pintype "bidirectional+no_connect"))
    )
    (net (code "110") (name "unconnected-(U1B-PT27C_JTAGENB-PadC10)") (class "Default")
      (node (ref "U1") (pin "C10") (pinfunction "PT27C_JTAGENB_C10") (pintype "bidirectional+no_connect"))
    )
    (net (code "111") (name "unconnected-(U1B-PT27D_PROGRAMN-PadB10)") (class "Default")
      (node (ref "U1") (pin "B10") (pinfunction "PT27D_PROGRAMN_B10") (pintype "bidirectional+no_connect"))
    )
    (net (code "112") (name "unconnected-(U1B-PT28A-PadA11)") (class "Default")
      (node (ref "U1") (pin "A11") (pinfunction "PT28A_A11") (pintype "bidirectional+no_connect"))
    )
    (net (code "113") (name "unconnected-(U1B-PT28B-PadC11)") (class "Default")
      (node (ref "U1") (pin "C11") (pinfunction "PT28B_C11") (pintype "bidirectional+no_connect"))
    )
    (net (code "114") (name "unconnected-(U1B-PT32A-PadF10)") (class "Default")
      (node (ref "U1") (pin "F10") (pinfunction "PT32A_F10") (pintype "bidirectional+no_connect"))
    )
    (net (code "115") (name "unconnected-(U1B-PT32B-PadD11)") (class "Default")
      (node (ref "U1") (pin "D11") (pinfunction "PT32B_D11") (pintype "bidirectional+no_connect"))
    )
    (net (code "116") (name "unconnected-(U1B-PT33A-PadB11)") (class "Default")
      (node (ref "U1") (pin "B11") (pinfunction "PT33A_B11") (pintype "bidirectional+no_connect"))
    )
    (net (code "117") (name "unconnected-(U1B-PT33B-PadA12)") (class "Default")
      (node (ref "U1") (pin "A12") (pinfunction "PT33B_A12") (pintype "bidirectional+no_connect"))
    )
    (net (code "118") (name "unconnected-(U1B-PT34A-PadB13)") (class "Default")
      (node (ref "U1") (pin "B13") (pinfunction "PT34A_B13") (pintype "bidirectional+no_connect"))
    )
    (net (code "119") (name "unconnected-(U1B-PT34B-PadA14)") (class "Default")
      (node (ref "U1") (pin "A14") (pinfunction "PT34B_A14") (pintype "bidirectional+no_connect"))
    )
    (net (code "120") (name "unconnected-(U1B-PT35A-PadC12)") (class "Default")
      (node (ref "U1") (pin "C12") (pinfunction "PT35A_C12") (pintype "bidirectional+no_connect"))
    )
    (net (code "121") (name "unconnected-(U1B-PT35B-PadB12)") (class "Default")
      (node (ref "U1") (pin "B12") (pinfunction "PT35B_B12") (pintype "bidirectional+no_connect"))
    )
    (net (code "122") (name "unconnected-(U1B-PT36A-PadB14)") (class "Default")
      (node (ref "U1") (pin "B14") (pinfunction "PT36A_B14") (pintype "bidirectional+no_connect"))
    )
    (net (code "123") (name "unconnected-(U1B-PT36B-PadA15)") (class "Default")
      (node (ref "U1") (pin "A15") (pinfunction "PT36B_A15") (pintype "bidirectional+no_connect"))
    )
    (net (code "124") (name "unconnected-(U1D-PB4A-PadP4)") (class "Default")
      (node (ref "U1") (pin "P4") (pinfunction "PB4A_P4") (pintype "bidirectional+no_connect"))
    )
    (net (code "125") (name "unconnected-(U1D-PB6B-PadP5)") (class "Default")
      (node (ref "U1") (pin "P5") (pinfunction "PB6B_P5") (pintype "bidirectional+no_connect"))
    )
    (net (code "126") (name "unconnected-(U1D-PB10A-PadN6)") (class "Default")
      (node (ref "U1") (pin "N6") (pinfunction "PB10A_N6") (pintype "bidirectional+no_connect"))
    )
    (net (code "127") (name "unconnected-(U1D-PB10B-PadL7)") (class "Default")
      (node (ref "U1") (pin "L7") (pinfunction "PB10B_L7") (pintype "bidirectional+no_connect"))
    )
    (net (code "128") (name "unconnected-(U1D-PB12A_MCLK_CCLK-PadP6)") (class "Default")
      (node (ref "U1") (pin "P6") (pinfunction "PB12A_MCLK_CCLK_P6") (pintype "bidirectional+no_connect"))
    )
    (net (code "129") (name "unconnected-(U1D-PB13A-PadR7)") (class "Default")
      (node (ref "U1") (pin "R7") (pinfunction "PB13A_R7") (pintype "bidirectional+no_connect"))
    )
    (net (code "130") (name "unconnected-(U1D-PB13B-PadP7)") (class "Default")
      (node (ref "U1") (pin "P7") (pinfunction "PB13B_P7") (pintype "bidirectional+no_connect"))
    )
    (net (code "131") (name "unconnected-(U1D-PB13C-PadM7)") (class "Default")
      (node (ref "U1") (pin "M7") (pinfunction "PB13C_M7") (pintype "bidirectional+no_connect"))
    )
    (net (code "132") (name "unconnected-(U1D-PB13D-PadN7)") (class "Default")
      (node (ref "U1") (pin "N7") (pinfunction "PB13D_N7") (pintype "bidirectional+no_connect"))
    )
    (net (code "133") (name "unconnected-(U1D-PB15A-PadM6)") (class "Default")
      (node (ref "U1") (pin "M6") (pinfunction "PB15A_M6") (pintype "bidirectional+no_connect"))
    )
    (net (code "134") (name "unconnected-(U1D-PB15B-PadL8)") (class "Default")
      (node (ref "U1") (pin "L8") (pinfunction "PB15B_L8") (pintype "bidirectional+no_connect"))
    )
    (net (code "135") (name "unconnected-(U1D-PB18A-PadP8)") (class "Default")
      (node (ref "U1") (pin "P8") (pinfunction "PB18A_P8") (pintype "bidirectional+no_connect"))
    )
    (net (code "136") (name "unconnected-(U1D-PB18C-PadN8)") (class "Default")
      (node (ref "U1") (pin "N8") (pinfunction "PB18C_N8") (pintype "bidirectional+no_connect"))
    )
    (net (code "137") (name "unconnected-(U1D-PB18D-PadL9)") (class "Default")
      (node (ref "U1") (pin "L9") (pinfunction "PB18D_L9") (pintype "bidirectional+no_connect"))
    )
    (net (code "138") (name "unconnected-(U1D-PB21A-PadM8)") (class "Default")
      (node (ref "U1") (pin "M8") (pinfunction "PB21A_M8") (pintype "bidirectional+no_connect"))
    )
    (net (code "139") (name "unconnected-(U1D-PB21B-PadN9)") (class "Default")
      (node (ref "U1") (pin "N9") (pinfunction "PB21B_N9") (pintype "bidirectional+no_connect"))
    )
    (net (code "140") (name "unconnected-(U1D-PB23B_PCLKC21-PadP9)") (class "Default")
      (node (ref "U1") (pin "P9") (pinfunction "PB23B_PCLKC21_P9") (pintype "bidirectional+no_connect"))
    )
    (net (code "141") (name "unconnected-(U1D-PB26C-PadM9)") (class "Default")
      (node (ref "U1") (pin "M9") (pinfunction "PB26C_M9") (pintype "bidirectional+no_connect"))
    )
    (net (code "142") (name "unconnected-(U1D-PB26D-PadL10)") (class "Default")
      (node (ref "U1") (pin "L10") (pinfunction "PB26D_L10") (pintype "bidirectional+no_connect"))
    )
    (net (code "143") (name "unconnected-(U1D-PB28A-PadN10)") (class "Default")
      (node (ref "U1") (pin "N10") (pinfunction "PB28A_N10") (pintype "bidirectional+no_connect"))
    )
    (net (code "144") (name "unconnected-(U1D-PB28B-PadM11)") (class "Default")
      (node (ref "U1") (pin "M11") (pinfunction "PB28B_M11") (pintype "bidirectional+no_connect"))
    )
    (net (code "145") (name "unconnected-(U1D-PB29A-PadP10)") (class "Default")
      (node (ref "U1") (pin "P10") (pinfunction "PB29A_P10") (pintype "bidirectional+no_connect"))
    )
    (net (code "146") (name "unconnected-(U1D-PB31B-PadP11)") (class "Default")
      (node (ref "U1") (pin "P11") (pinfunction "PB31B_P11") (pintype "bidirectional+no_connect"))
    )
    (net (code "147") (name "unconnected-(U1D-PB31C-PadM10)") (class "Default")
      (node (ref "U1") (pin "M10") (pinfunction "PB31C_M10") (pintype "bidirectional+no_connect"))
    )
    (net (code "148") (name "unconnected-(U1D-PB31D-PadN11)") (class "Default")
      (node (ref "U1") (pin "N11") (pinfunction "PB31D_N11") (pintype "bidirectional+no_connect"))
    )
    (net (code "149") (name "unconnected-(U1D-PB37A-PadP12)") (class "Default")
      (node (ref "U1") (pin "P12") (pinfunction "PB37A_P12") (pintype "bidirectional+no_connect"))
    )
    (net (code "150") (name "unconnected-(U1E-PL19B-PadL3)") (class "Default")
      (node (ref "U1") (pin "L3") (pinfunction "PL19B_L3") (pintype "bidirectional+no_connect"))
    )
    (net (code "151") (name "unconnected-(U1E-PL19C-PadK4)") (class "Default")
      (node (ref "U1") (pin "K4") (pinfunction "PL19C_K4") (pintype "bidirectional+no_connect"))
    )
    (net (code "152") (name "unconnected-(U1E-PL19D-PadL5)") (class "Default")
      (node (ref "U1") (pin "L5") (pinfunction "PL19D_L5") (pintype "bidirectional+no_connect"))
    )
    (net (code "153") (name "unconnected-(U1E-PL21C-PadK5)") (class "Default")
      (node (ref "U1") (pin "K5") (pinfunction "PL21C_K5") (pintype "bidirectional+no_connect"))
    )
    (net (code "154") (name "unconnected-(U1E-PL21D-PadL4)") (class "Default")
      (node (ref "U1") (pin "L4") (pinfunction "PL21D_L4") (pintype "bidirectional+no_connect"))
    )
    (net (code "155") (name "unconnected-(U1E-PL23C-PadN2)") (class "Default")
      (node (ref "U1") (pin "N2") (pinfunction "PL23C_N2") (pintype "bidirectional+no_connect"))
    )
    (net (code "156") (name "unconnected-(U1E-PL23D-PadP1)") (class "Default")
      (node (ref "U1") (pin "P1") (pinfunction "PL23D_P1") (pintype "bidirectional+no_connect"))
    )
    (net (code "157") (name "unconnected-(U1E-PL24A-PadM3)") (class "Default")
      (node (ref "U1") (pin "M3") (pinfunction "PL24A_M3") (pintype "bidirectional+no_connect"))
    )
    (net (code "158") (name "unconnected-(U1E-PL24B-PadN1)") (class "Default")
      (node (ref "U1") (pin "N1") (pinfunction "PL24B_N1") (pintype "bidirectional+no_connect"))
    )
    (net (code "159") (name "unconnected-(U1E-PL25B-PadN3)") (class "Default")
      (node (ref "U1") (pin "N3") (pinfunction "PL25B_N3") (pintype "bidirectional+no_connect"))
    )
    (net (code "160") (name "unconnected-(U1E-PL25C-PadR1)") (class "Default")
      (node (ref "U1") (pin "R1") (pinfunction "PL25C_R1") (pintype "bidirectional+no_connect"))
    )
    (net (code "161") (name "unconnected-(U1E-PL25D-PadP2)") (class "Default")
      (node (ref "U1") (pin "P2") (pinfunction "PL25D_P2") (pintype "bidirectional+no_connect"))
    )
    (net (code "162") (name "unconnected-(U1F-PL10A-PadG1)") (class "Default")
      (node (ref "U1") (pin "G1") (pinfunction "PL10A_G1") (pintype "bidirectional+no_connect"))
    )
    (net (code "163") (name "unconnected-(U1F-PL10B-PadH2)") (class "Default")
      (node (ref "U1") (pin "H2") (pinfunction "PL10B_H2") (pintype "bidirectional+no_connect"))
    )
    (net (code "164") (name "unconnected-(U1F-PL10C-PadH4)") (class "Default")
      (node (ref "U1") (pin "H4") (pinfunction "PL10C_H4") (pintype "bidirectional+no_connect"))
    )
    (net (code "165") (name "unconnected-(U1F-PL10D-PadJ6)") (class "Default")
      (node (ref "U1") (pin "J6") (pinfunction "PL10D_J6") (pintype "bidirectional+no_connect"))
    )
    (net (code "166") (name "unconnected-(U1F-PL11A-PadH3)") (class "Default")
      (node (ref "U1") (pin "H3") (pinfunction "PL11A_H3") (pintype "bidirectional+no_connect"))
    )
    (net (code "167") (name "unconnected-(U1F-PL11B-PadH1)") (class "Default")
      (node (ref "U1") (pin "H1") (pinfunction "PL11B_H1") (pintype "bidirectional+no_connect"))
    )
    (net (code "168") (name "unconnected-(U1F-PL12A_PCLKT40-PadJ1)") (class "Default")
      (node (ref "U1") (pin "J1") (pinfunction "PL12A_PCLKT40_J1") (pintype "bidirectional+no_connect"))
    )
    (net (code "169") (name "unconnected-(U1F-PL12B_PCLKC40-PadJ3)") (class "Default")
      (node (ref "U1") (pin "J3") (pinfunction "PL12B_PCLKC40_J3") (pintype "bidirectional+no_connect"))
    )
    (net (code "170") (name "unconnected-(U1F-PL15A-PadJ2)") (class "Default")
      (node (ref "U1") (pin "J2") (pinfunction "PL15A_J2") (pintype "bidirectional+no_connect"))
    )
    (net (code "171") (name "unconnected-(U1F-PL15B-PadK1)") (class "Default")
      (node (ref "U1") (pin "K1") (pinfunction "PL15B_K1") (pintype "bidirectional+no_connect"))
    )
    (net (code "172") (name "unconnected-(U1F-PL15C-PadH5)") (class "Default")
      (node (ref "U1") (pin "H5") (pinfunction "PL15C_H5") (pintype "bidirectional+no_connect"))
    )
    (net (code "173") (name "unconnected-(U1F-PL15D-PadJ4)") (class "Default")
      (node (ref "U1") (pin "J4") (pinfunction "PL15D_J4") (pintype "bidirectional+no_connect"))
    )
    (net (code "174") (name "unconnected-(U1F-PL16C-PadJ5)") (class "Default")
      (node (ref "U1") (pin "J5") (pinfunction "PL16C_J5") (pintype "bidirectional+no_connect"))
    )
    (net (code "175") (name "unconnected-(U1F-PL16D-PadK6)") (class "Default")
      (node (ref "U1") (pin "K6") (pinfunction "PL16D_K6") (pintype "bidirectional+no_connect"))
    )
    (net (code "176") (name "unconnected-(U1F-PL17A-PadK3)") (class "Default")
      (node (ref "U1") (pin "K3") (pinfunction "PL17A_K3") (pintype "bidirectional+no_connect"))
    )
    (net (code "177") (name "unconnected-(U1F-PL17B-PadK2)") (class "Default")
      (node (ref "U1") (pin "K2") (pinfunction "PL17B_K2") (pintype "bidirectional+no_connect"))
    )
    (net (code "178") (name "unconnected-(U1G-PL2C-PadB1)") (class "Default")
      (node (ref "U1") (pin "B1") (pinfunction "PL2C_B1") (pintype "bidirectional+no_connect"))
    )
    (net (code "179") (name "unconnected-(U1G-PL2D-PadC2)") (class "Default")
      (node (ref "U1") (pin "C2") (pinfunction "PL2D_C2") (pintype "bidirectional+no_connect"))
    )
    (net (code "180") (name "unconnected-(U1G-PL3A_LGPLLTFB-PadD3)") (class "Default")
      (node (ref "U1") (pin "D3") (pinfunction "PL3A_LGPLLTFB_D3") (pintype "bidirectional+no_connect"))
    )
    (net (code "181") (name "unconnected-(U1G-PL3B_LGPLLCFB-PadD1)") (class "Default")
      (node (ref "U1") (pin "D1") (pinfunction "PL3B_LGPLLCFB_D1") (pintype "bidirectional+no_connect"))
    )
    (net (code "182") (name "unconnected-(U1G-PL4B_LGPLLCIN-PadE3)") (class "Default")
      (node (ref "U1") (pin "E3") (pinfunction "PL4B_LGPLLCIN_E3") (pintype "bidirectional+no_connect"))
    )
    (net (code "183") (name "unconnected-(U1G-PL4C-PadC1)") (class "Default")
      (node (ref "U1") (pin "C1") (pinfunction "PL4C_C1") (pintype "bidirectional+no_connect"))
    )
    (net (code "184") (name "unconnected-(U1G-PL4D-PadD2)") (class "Default")
      (node (ref "U1") (pin "D2") (pinfunction "PL4D_D2") (pintype "bidirectional+no_connect"))
    )
    (net (code "185") (name "unconnected-(U1G-PL6A_PCLKT50-PadE1)") (class "Default")
      (node (ref "U1") (pin "E1") (pinfunction "PL6A_PCLKT50_E1") (pintype "bidirectional+no_connect"))
    )
    (net (code "186") (name "unconnected-(U1G-PL6B_PCLKC50-PadF2)") (class "Default")
      (node (ref "U1") (pin "F2") (pinfunction "PL6B_PCLKC50_F2") (pintype "bidirectional+no_connect"))
    )
    (net (code "187") (name "unconnected-(U1G-PL6C-PadF4)") (class "Default")
      (node (ref "U1") (pin "F4") (pinfunction "PL6C_F4") (pintype "bidirectional+no_connect"))
    )
    (net (code "188") (name "unconnected-(U1G-PL6D-PadG6)") (class "Default")
      (node (ref "U1") (pin "G6") (pinfunction "PL6D_G6") (pintype "bidirectional+no_connect"))
    )
    (net (code "189") (name "unconnected-(U1G-PL7C-PadG5)") (class "Default")
      (node (ref "U1") (pin "G5") (pinfunction "PL7C_G5") (pintype "bidirectional+no_connect"))
    )
    (net (code "190") (name "unconnected-(U1G-PL7D-PadG4)") (class "Default")
      (node (ref "U1") (pin "G4") (pinfunction "PL7D_G4") (pintype "bidirectional+no_connect"))
    )
    (net (code "191") (name "unconnected-(U1G-PL8A-PadF3)") (class "Default")
      (node (ref "U1") (pin "F3") (pinfunction "PL8A_F3") (pintype "bidirectional+no_connect"))
    )
    (net (code "192") (name "unconnected-(U1G-PL9A-PadG2)") (class "Default")
      (node (ref "U1") (pin "G2") (pinfunction "PL9A_G2") (pintype "bidirectional+no_connect"))
    )
    (net (code "193") (name "unconnected-(U1G-PL9B-PadG3)") (class "Default")
      (node (ref "U1") (pin "G3") (pinfunction "PL9B_G3") (pintype "bidirectional+no_connect"))
    )
    (net (code "194") (name "unconnected-(U1G-PL9C-PadF5)") (class "Default")
      (node (ref "U1") (pin "F5") (pinfunction "PL9C_F5") (pintype "bidirectional+no_connect"))
    )
    (net (code "195") (name "unconnected-(U1G-PL9D-PadH6)") (class "Default")
      (node (ref "U1") (pin "H6") (pinfunction "PL9D_H6") (pintype "bidirectional+no_connect"))
    )
  )
)
